# F103-DRV8313.net
KiCad netlist of a schematic drawn in Altium Designer
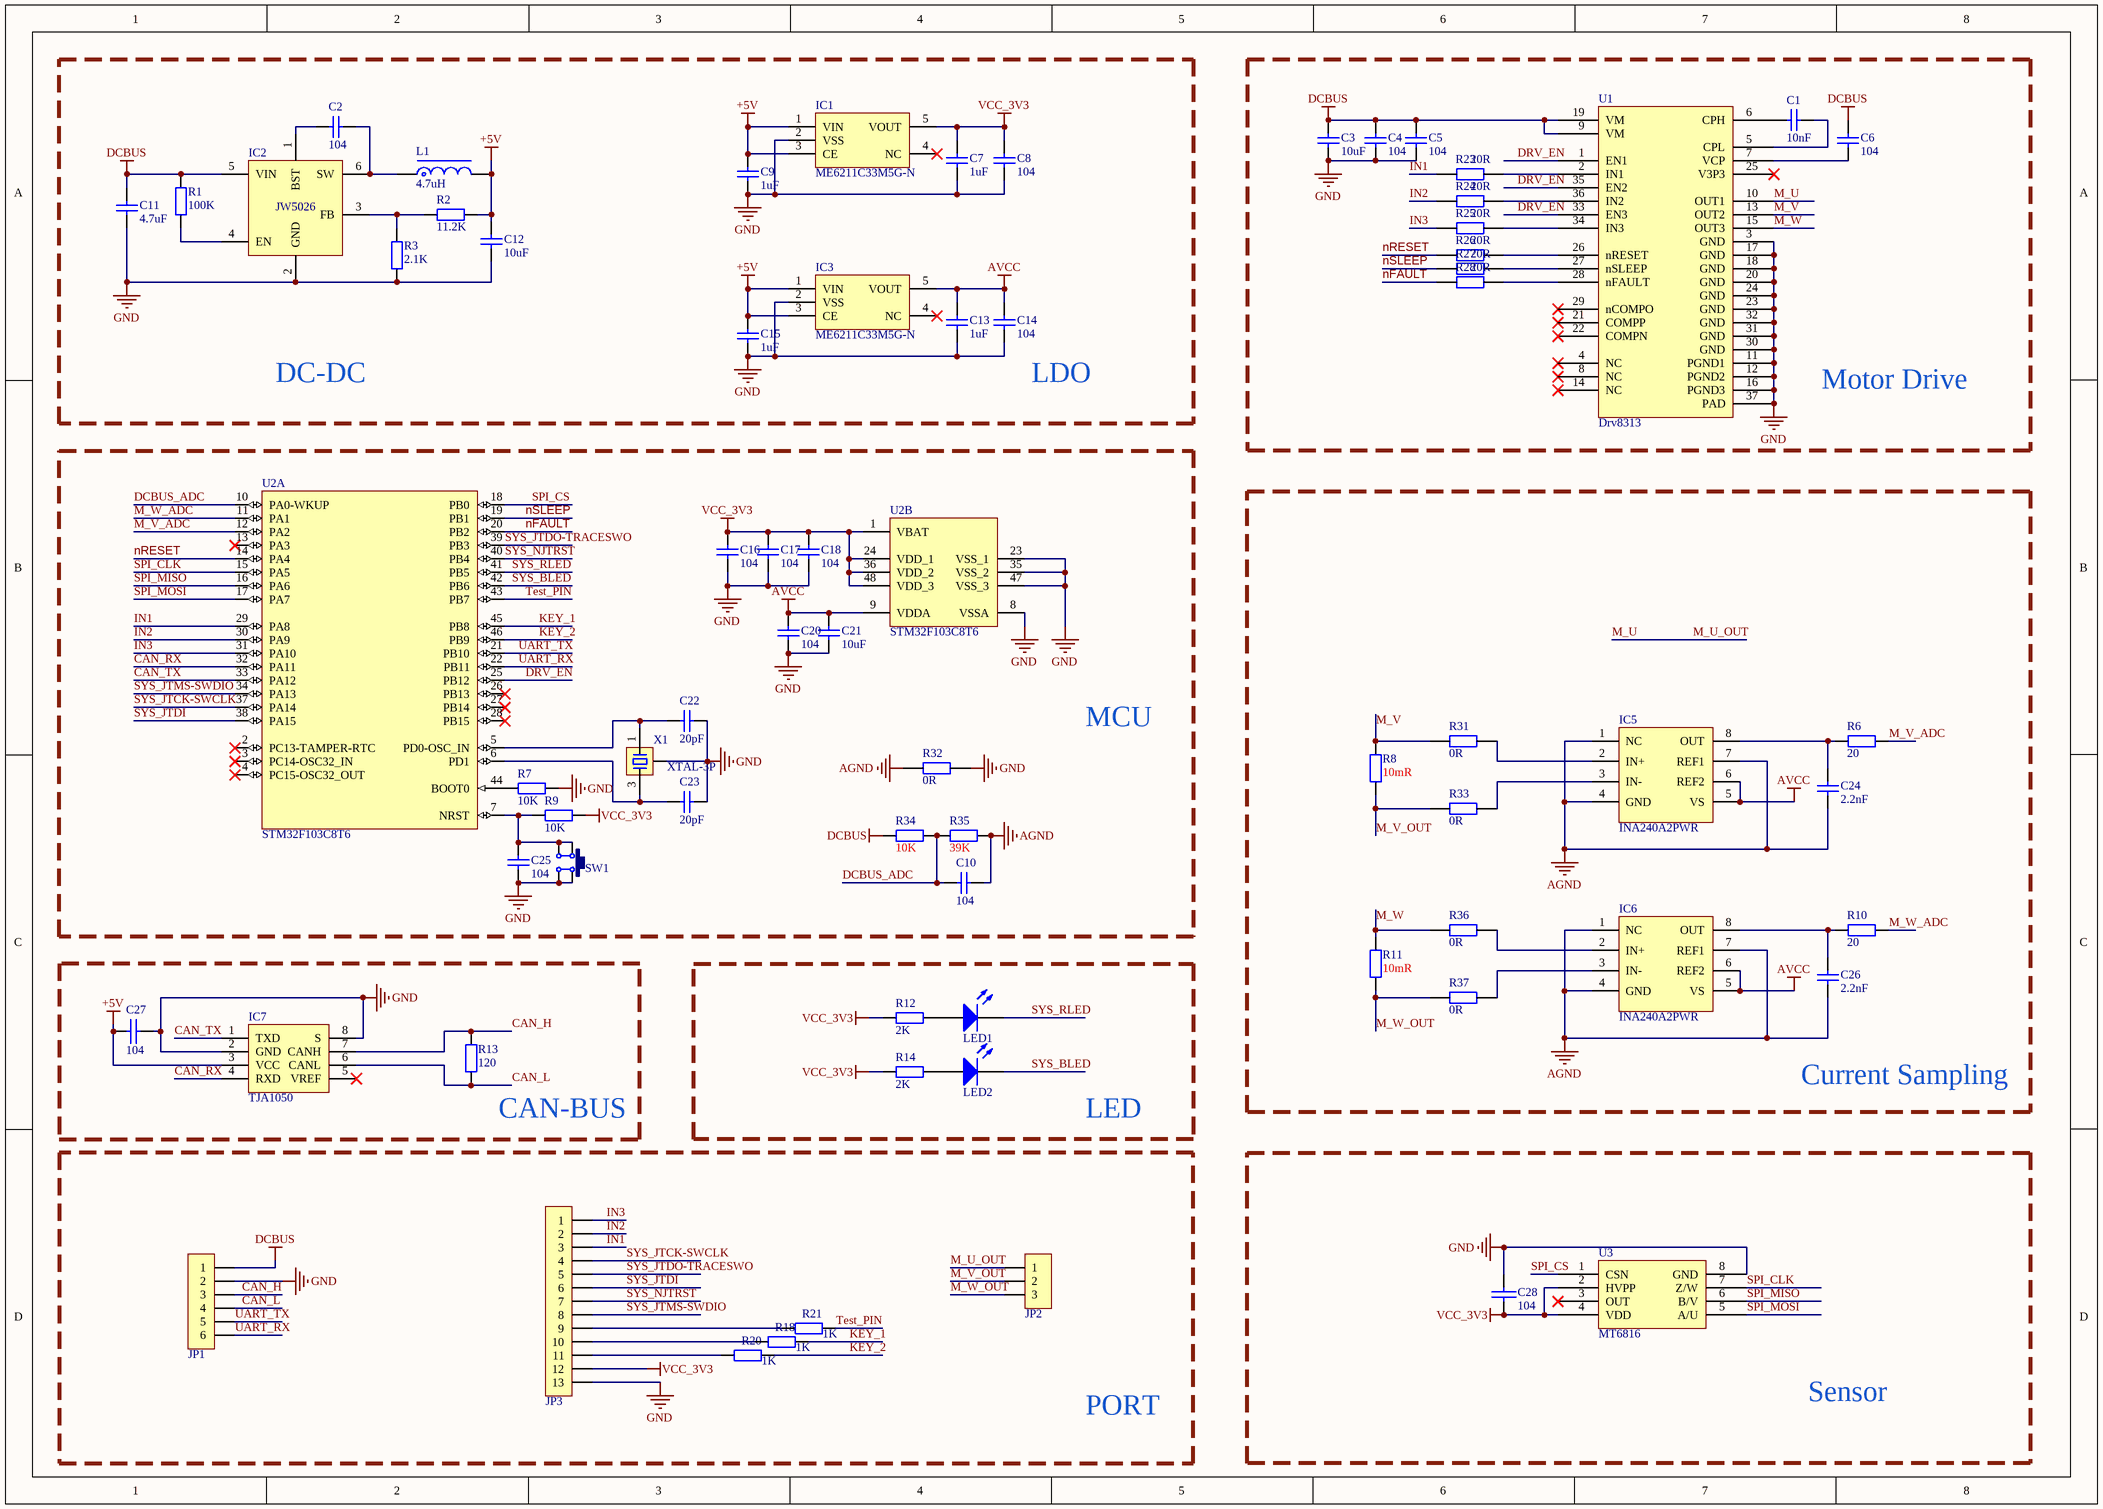
[diagram p0: F103-DRV8313.SchDoc]

(export (version "E")
  (design (tool "Eeschema 10.0.6"))
  (components
    (comp (ref "C1")
      (value "10nF")
      (footprint "C0603_L")
      (description "贴片电容/MLCC电容")
      (libsource (lib "0.1 - 电阻-电容-电感-晶振-晶体-磁珠-电位器-法拉电容-馈通电容") (part "C"))
    )
    (comp (ref "C2")
      (value "104")
      (footprint "C0603_L")
      (description "贴片电容/MLCC电容")
      (libsource (lib "0.1 - 电阻-电容-电感-晶振-晶体-磁珠-电位器-法拉电容-馈通电容") (part "C"))
    )
    (comp (ref "C3")
      (value "10uF")
      (footprint "C0603_L")
      (description "贴片电容/MLCC电容")
      (libsource (lib "0.1 - 电阻-电容-电感-晶振-晶体-磁珠-电位器-法拉电容-馈通电容") (part "C"))
    )
    (comp (ref "C4")
      (value "104")
      (footprint "C0603_L")
      (description "贴片电容/MLCC电容")
      (libsource (lib "0.1 - 电阻-电容-电感-晶振-晶体-磁珠-电位器-法拉电容-馈通电容") (part "C"))
    )
    (comp (ref "C5")
      (value "104")
      (footprint "C0603_L")
      (description "贴片电容/MLCC电容")
      (libsource (lib "0.1 - 电阻-电容-电感-晶振-晶体-磁珠-电位器-法拉电容-馈通电容") (part "C"))
    )
    (comp (ref "C6")
      (value "104")
      (footprint "C0603_L")
      (description "贴片电容/MLCC电容")
      (libsource (lib "0.1 - 电阻-电容-电感-晶振-晶体-磁珠-电位器-法拉电容-馈通电容") (part "C"))
    )
    (comp (ref "C7")
      (value "1uF")
      (footprint "C0603_L")
      (description "贴片电容/MLCC电容")
      (libsource (lib "0.1 - 电阻-电容-电感-晶振-晶体-磁珠-电位器-法拉电容-馈通电容") (part "C"))
    )
    (comp (ref "C8")
      (value "104")
      (footprint "C0603_L")
      (description "贴片电容/MLCC电容")
      (libsource (lib "0.1 - 电阻-电容-电感-晶振-晶体-磁珠-电位器-法拉电容-馈通电容") (part "C"))
    )
    (comp (ref "C9")
      (value "1uF")
      (footprint "C0603_L")
      (description "贴片电容/MLCC电容")
      (libsource (lib "0.1 - 电阻-电容-电感-晶振-晶体-磁珠-电位器-法拉电容-馈通电容") (part "C"))
    )
    (comp (ref "C10")
      (value "104")
      (footprint "C0402_L")
      (description "贴片电容/MLCC电容")
      (libsource (lib "0.1 - 电阻-电容-电感-晶振-晶体-磁珠-电位器-法拉电容-馈通电容") (part "C"))
    )
    (comp (ref "C11")
      (value "4.7uF")
      (footprint "C0603_L")
      (description "贴片电容/MLCC电容")
      (libsource (lib "0.1 - 电阻-电容-电感-晶振-晶体-磁珠-电位器-法拉电容-馈通电容") (part "C"))
    )
    (comp (ref "C12")
      (value "10uF")
      (footprint "C0603_L")
      (description "贴片电容/MLCC电容")
      (libsource (lib "0.1 - 电阻-电容-电感-晶振-晶体-磁珠-电位器-法拉电容-馈通电容") (part "C"))
    )
    (comp (ref "C13")
      (value "1uF")
      (footprint "C0603_L")
      (description "贴片电容/MLCC电容")
      (libsource (lib "0.1 - 电阻-电容-电感-晶振-晶体-磁珠-电位器-法拉电容-馈通电容") (part "C"))
    )
    (comp (ref "C14")
      (value "104")
      (footprint "C0603_L")
      (description "贴片电容/MLCC电容")
      (libsource (lib "0.1 - 电阻-电容-电感-晶振-晶体-磁珠-电位器-法拉电容-馈通电容") (part "C"))
    )
    (comp (ref "C15")
      (value "1uF")
      (footprint "C0603_L")
      (description "贴片电容/MLCC电容")
      (libsource (lib "0.1 - 电阻-电容-电感-晶振-晶体-磁珠-电位器-法拉电容-馈通电容") (part "C"))
    )
    (comp (ref "C16")
      (value "104")
      (footprint "C0402_L")
      (description "贴片电容/MLCC电容")
      (libsource (lib "0.1 - 电阻-电容-电感-晶振-晶体-磁珠-电位器-法拉电容-馈通电容") (part "C"))
    )
    (comp (ref "C17")
      (value "104")
      (footprint "C0402_L")
      (description "贴片电容/MLCC电容")
      (libsource (lib "0.1 - 电阻-电容-电感-晶振-晶体-磁珠-电位器-法拉电容-馈通电容") (part "C"))
    )
    (comp (ref "C18")
      (value "104")
      (footprint "C0402_L")
      (description "贴片电容/MLCC电容")
      (libsource (lib "0.1 - 电阻-电容-电感-晶振-晶体-磁珠-电位器-法拉电容-馈通电容") (part "C"))
    )
    (comp (ref "C20")
      (value "104")
      (footprint "C0402_L")
      (description "贴片电容/MLCC电容")
      (libsource (lib "0.1 - 电阻-电容-电感-晶振-晶体-磁珠-电位器-法拉电容-馈通电容") (part "C"))
    )
    (comp (ref "C21")
      (value "10uF")
      (footprint "C0402_L")
      (description "贴片电容/MLCC电容")
      (libsource (lib "0.1 - 电阻-电容-电感-晶振-晶体-磁珠-电位器-法拉电容-馈通电容") (part "C"))
    )
    (comp (ref "C22")
      (value "20pF")
      (footprint "C0402_L")
      (description "贴片电容/MLCC电容")
      (libsource (lib "0.1 - 电阻-电容-电感-晶振-晶体-磁珠-电位器-法拉电容-馈通电容") (part "C"))
    )
    (comp (ref "C23")
      (value "20pF")
      (footprint "C0402_L")
      (description "贴片电容/MLCC电容")
      (libsource (lib "0.1 - 电阻-电容-电感-晶振-晶体-磁珠-电位器-法拉电容-馈通电容") (part "C"))
    )
    (comp (ref "C24")
      (value "2.2nF")
      (footprint "C0402_L")
      (description "贴片电容/MLCC电容")
      (libsource (lib "0.1 - 电阻-电容-电感-晶振-晶体-磁珠-电位器-法拉电容-馈通电容") (part "C"))
    )
    (comp (ref "C25")
      (value "104")
      (footprint "C0402_L")
      (description "贴片电容/MLCC电容")
      (libsource (lib "0.1 - 电阻-电容-电感-晶振-晶体-磁珠-电位器-法拉电容-馈通电容") (part "C"))
    )
    (comp (ref "C26")
      (value "2.2nF")
      (footprint "C0402_L")
      (description "贴片电容/MLCC电容")
      (libsource (lib "0.1 - 电阻-电容-电感-晶振-晶体-磁珠-电位器-法拉电容-馈通电容") (part "C"))
    )
    (comp (ref "C27")
      (value "104")
      (footprint "C0402_L")
      (description "Capacitor")
      (libsource (lib "SCHLIB") (part "Capacitor"))
    )
    (comp (ref "C28")
      (value "104")
      (footprint "C0402_L")
      (description "Capacitor")
      (libsource (lib "SCHLIB") (part "Capacitor"))
    )
    (comp (ref "IC1")
      (value "ME6211C33M5G-N")
      (footprint "SOT23-5N")
      (libsource (lib "1.0 - 常见芯片") (part "ME6211C33M5G-N"))
    )
    (comp (ref "IC2")
      (value "JW5026")
      (footprint "SOT23-6M")
      (libsource (lib "1.0 - 常见芯片") (part "JW5026 40V 1A"))
    )
    (comp (ref "IC3")
      (value "ME6211C33M5G-N")
      (footprint "SOT23-5N")
      (libsource (lib "1.0 - 常见芯片") (part "ME6211C33M5G-N"))
    )
    (comp (ref "IC5")
      (value "INA240A2PWR")
      (footprint "TSSOP8_N")
      (description "运放芯片")
      (libsource (lib "1.0 - 常见芯片") (part "INA240A2PWR"))
    )
    (comp (ref "IC6")
      (value "INA240A2PWR")
      (footprint "TSSOP8_N")
      (description "运放芯片")
      (libsource (lib "1.0 - 常见芯片") (part "INA240A2PWR"))
    )
    (comp (ref "IC7")
      (value "TJA1050")
      (footprint "SOP8_N")
      (description "CAN总线收发芯片")
      (libsource (lib "1.0 - 常见芯片") (part "TJA1050"))
    )
    (comp (ref "JP1")
      (value "HDR-1X6")
      (footprint "GH-1.25-6P")
      (description "6P连接器")
      (libsource (lib "5.1 - 1.25mm连接器(FPC1.25_GH1.25_MX1.25)") (part "Header 6"))
    )
    (comp (ref "JP2")
      (value "CON-3P")
      (footprint "SH1.0-WT-3P")
      (description "3P连接器")
      (libsource (lib "5.0 - 1.00mm连接器(FPC1.0_SH1.0_1.0排针排母)") (part "Header 3"))
    )
    (comp (ref "JP3")
      (value "HDR-1X13")
      (footprint "FPC0.5-WT-13P")
      (description "13P连接器")
      (libsource (lib "5.1 - 1.25mm连接器(FPC1.25_GH1.25_MX1.25)") (part "Header 13"))
    )
    (comp (ref "L1")
      (value "4.7uH")
      (footprint "CD31")
      (description "功率屏蔽电感")
      (libsource (lib "0.1 - 电阻-电容-电感") (part "L-CDRH"))
    )
    (comp (ref "LED1")
      (value "LED")
      (footprint "LED 0603B")
      (description "发光二极管")
      (libsource (lib "0.3 - LED发光二极管") (part "LED"))
    )
    (comp (ref "LED2")
      (value "LED")
      (footprint "LED 0603B")
      (description "发光二极管")
      (libsource (lib "0.3 - LED发光二极管") (part "LED"))
    )
    (comp (ref "R1")
      (value "100K")
      (footprint "R 0402_L")
      (description "贴片电阻")
      (libsource (lib "0.1 - 电阻-电容-电感") (part "R"))
    )
    (comp (ref "R2")
      (value "11.2K")
      (footprint "R 0402_L")
      (description "贴片电阻")
      (libsource (lib "0.1 - 电阻-电容-电感") (part "R"))
    )
    (comp (ref "R3")
      (value "2.1K")
      (footprint "R 0402_L")
      (description "贴片电阻")
      (libsource (lib "0.1 - 电阻-电容-电感") (part "R"))
    )
    (comp (ref "R6")
      (value "20")
      (footprint "R 0402_L")
      (description "贴片电阻")
      (libsource (lib "0.1 - 电阻-电容-电感") (part "R"))
    )
    (comp (ref "R7")
      (value "10K")
      (footprint "R0402_L")
      (description "贴片电阻")
      (libsource (lib "0.1 - 电阻-电容-电感-晶振-晶体-磁珠-电位器-法拉电容-馈通电容") (part "R"))
    )
    (comp (ref "R8")
      (value "10mR")
      (footprint "R0805_L")
      (description "电流检测电阻")
      (libsource (lib "0.1 - 电阻-电容-电感") (part "R-I"))
    )
    (comp (ref "R9")
      (value "10K")
      (footprint "R0402_L")
      (description "贴片电阻")
      (libsource (lib "0.1 - 电阻-电容-电感-晶振-晶体-磁珠-电位器-法拉电容-馈通电容") (part "R"))
    )
    (comp (ref "R10")
      (value "20")
      (footprint "R 0402_L")
      (description "贴片电阻")
      (libsource (lib "0.1 - 电阻-电容-电感") (part "R"))
    )
    (comp (ref "R11")
      (value "10mR")
      (footprint "R0805_L")
      (description "电流检测电阻")
      (libsource (lib "0.1 - 电阻-电容-电感") (part "R-I"))
    )
    (comp (ref "R12")
      (value "2K")
      (footprint "R 0402_L")
      (description "贴片电阻")
      (libsource (lib "0.1 - 电阻-电容-电感") (part "R"))
    )
    (comp (ref "R13")
      (value "120")
      (footprint "R0402_L")
      (description "贴片电阻")
      (libsource (lib "0.1 - 电阻-电容-电感") (part "R"))
    )
    (comp (ref "R14")
      (value "2K")
      (footprint "R 0402_L")
      (description "贴片电阻")
      (libsource (lib "0.1 - 电阻-电容-电感") (part "R"))
    )
    (comp (ref "R18")
      (value "1K")
      (footprint "R0402_L")
      (description "贴片电阻")
      (libsource (lib "0.1 - 电阻-电容-电感") (part "R"))
    )
    (comp (ref "R20")
      (value "1K")
      (footprint "R0402_L")
      (description "贴片电阻")
      (libsource (lib "0.1 - 电阻-电容-电感") (part "R"))
    )
    (comp (ref "R21")
      (value "1K")
      (footprint "R0402_L")
      (description "贴片电阻")
      (libsource (lib "0.1 - 电阻-电容-电感") (part "R"))
    )
    (comp (ref "R23")
      (value "20R")
      (footprint "R0402_L")
      (description "10K")
      (libsource (lib "SCHLIB") (part "RES_R"))
    )
    (comp (ref "R24")
      (value "20R")
      (footprint "R0402_L")
      (description "10K")
      (libsource (lib "SCHLIB") (part "RES_R"))
    )
    (comp (ref "R25")
      (value "20R")
      (footprint "R0402_L")
      (description "10K")
      (libsource (lib "SCHLIB") (part "RES_R"))
    )
    (comp (ref "R26")
      (value "20R")
      (footprint "R0402_L")
      (description "10K")
      (libsource (lib "SCHLIB") (part "RES_R"))
    )
    (comp (ref "R27")
      (value "20R")
      (footprint "R0402_L")
      (description "10K")
      (libsource (lib "SCHLIB") (part "RES_R"))
    )
    (comp (ref "R28")
      (value "20R")
      (footprint "R0402_L")
      (description "10K")
      (libsource (lib "SCHLIB") (part "RES_R"))
    )
    (comp (ref "R31")
      (value "0R")
      (footprint "R0402_L")
      (description "10K")
      (libsource (lib "SCHLIB") (part "RES_R"))
    )
    (comp (ref "R32")
      (value "0R")
      (footprint "R0402_L")
      (description "10K")
      (libsource (lib "SCHLIB") (part "RES_R"))
    )
    (comp (ref "R33")
      (value "0R")
      (footprint "R0402_L")
      (description "10K")
      (libsource (lib "SCHLIB") (part "RES_R"))
    )
    (comp (ref "R34")
      (value "10K")
      (footprint "R0402_L")
      (description "贴片电阻")
      (libsource (lib "0.1 - 电阻-电容-电感-晶振-晶体-磁珠-电位器-法拉电容-馈通电容") (part "R"))
    )
    (comp (ref "R35")
      (value "39K")
      (footprint "R0402_L")
      (description "贴片电阻")
      (libsource (lib "0.1 - 电阻-电容-电感-晶振-晶体-磁珠-电位器-法拉电容-馈通电容") (part "R"))
    )
    (comp (ref "R36")
      (value "0R")
      (footprint "R0402_L")
      (description "10K")
      (libsource (lib "SCHLIB") (part "RES_R"))
    )
    (comp (ref "R37")
      (value "0R")
      (footprint "R0402_L")
      (description "10K")
      (libsource (lib "SCHLIB") (part "RES_R"))
    )
    (comp (ref "SW1")
      (value "6x6x5")
      (footprint "TSW SMD-2.9*3.9*2")
      (description "贴片6x6轻触开关")
      (libsource (lib "0.7 - 常用按键-开关") (part "TSW SMD-6x6"))
    )
    (comp (ref "U1")
      (value "Drv8313")
      (footprint "VFQFPN36_N")
      (libsource (lib "4.1 - 未分类器件") (part "Drv8313"))
    )
    (comp (ref "U2")
      (value "STM32F103C8T6")
      (footprint "LQFP48_N")
      (libsource (lib "2.4 - STM32 F1系列单片机") (part "STM32F103C8T6"))
    )
    (comp (ref "U3") (value "MT6816") (footprint "SOP8_N") (libsource (lib "4.1 - 未分类器件") (part "MT6816")))
    (comp (ref "X1")
      (value "XTAL-3P")
      (footprint "SMD3213-3P")
      (description "三脚无源晶振")
      (libsource (lib "2.0 - 保险丝-晶振-光耦") (part "XTAL-3P"))
    )
  )
  (nets
    (net (code "1") (name "+5V") (class "Default")
      (node (ref "C12") (pin "2") (pinfunction "2_2") (pintype "passive"))
      (node (ref "C15") (pin "2") (pinfunction "2_2") (pintype "passive"))
      (node (ref "C27") (pin "1") (pinfunction "1_1") (pintype "passive"))
      (node (ref "C9") (pin "2") (pinfunction "2_2") (pintype "passive"))
      (node (ref "IC1") (pin "1") (pinfunction "VIN_1") (pintype "passive"))
      (node (ref "IC1") (pin "3") (pinfunction "CE_3") (pintype "passive"))
      (node (ref "IC3") (pin "1") (pinfunction "VIN_1") (pintype "passive"))
      (node (ref "IC3") (pin "3") (pinfunction "CE_3") (pintype "passive"))
      (node (ref "IC7") (pin "3") (pinfunction "VCC_3") (pintype "passive"))
      (node (ref "L1") (pin "2") (pinfunction "2_2") (pintype "passive"))
      (node (ref "R2") (pin "1") (pinfunction "1_1") (pintype "passive"))
    )
    (net (code "2") (name "/CAN_H") (class "Default")
      (node (ref "IC7") (pin "7") (pinfunction "CANH_7") (pintype "passive"))
      (node (ref "JP1") (pin "3") (pinfunction "3_3") (pintype "passive"))
      (node (ref "R13") (pin "2") (pinfunction "2_2") (pintype "passive"))
    )
    (net (code "3") (name "/CAN_L") (class "Default")
      (node (ref "IC7") (pin "6") (pinfunction "CANL_6") (pintype "passive"))
      (node (ref "JP1") (pin "4") (pinfunction "4_4") (pintype "passive"))
      (node (ref "R13") (pin "1") (pinfunction "1_1") (pintype "passive"))
    )
    (net (code "4") (name "/CAN_RX") (class "Default")
      (node (ref "IC7") (pin "4") (pinfunction "RXD_4") (pintype "passive"))
      (node (ref "U2") (pin "32") (pinfunction "PA11_32") (pintype "bidirectional"))
    )
    (net (code "5") (name "/CAN_TX") (class "Default")
      (node (ref "IC7") (pin "1") (pinfunction "TXD_1") (pintype "passive"))
      (node (ref "U2") (pin "33") (pinfunction "PA12_33") (pintype "bidirectional"))
    )
    (net (code "6") (name "/DCBUS_ADC") (class "Default")
      (node (ref "C10") (pin "2") (pinfunction "2_2") (pintype "passive"))
      (node (ref "R34") (pin "1") (pinfunction "1_1") (pintype "passive"))
      (node (ref "R35") (pin "2") (pinfunction "2_2") (pintype "passive"))
      (node (ref "U2") (pin "10") (pinfunction "PA0-WKUP_10") (pintype "bidirectional"))
    )
    (net (code "7") (name "/DRV_EN") (class "Default")
      (node (ref "U1") (pin "1") (pinfunction "EN1_1") (pintype "passive"))
      (node (ref "U1") (pin "33") (pinfunction "EN3_33") (pintype "passive"))
      (node (ref "U1") (pin "35") (pinfunction "EN2_35") (pintype "passive"))
      (node (ref "U2") (pin "25") (pinfunction "PB12_25") (pintype "bidirectional"))
    )
    (net (code "8") (name "/IN1") (class "Default")
      (node (ref "JP3") (pin "3") (pinfunction "3_3") (pintype "passive"))
      (node (ref "R23") (pin "1") (pinfunction "1_1") (pintype "passive"))
      (node (ref "U2") (pin "29") (pinfunction "PA8_29") (pintype "bidirectional"))
    )
    (net (code "9") (name "/IN2") (class "Default")
      (node (ref "JP3") (pin "2") (pinfunction "2_2") (pintype "passive"))
      (node (ref "R24") (pin "1") (pinfunction "1_1") (pintype "passive"))
      (node (ref "U2") (pin "30") (pinfunction "PA9_30") (pintype "bidirectional"))
    )
    (net (code "10") (name "/IN3") (class "Default")
      (node (ref "JP3") (pin "1") (pinfunction "1_1") (pintype "passive"))
      (node (ref "R25") (pin "1") (pinfunction "1_1") (pintype "passive"))
      (node (ref "U2") (pin "31") (pinfunction "PA10_31") (pintype "bidirectional"))
    )
    (net (code "11") (name "/KEY_1") (class "Default")
      (node (ref "R18") (pin "1") (pinfunction "1_1") (pintype "passive"))
      (node (ref "U2") (pin "45") (pinfunction "PB8_45") (pintype "bidirectional"))
    )
    (net (code "12") (name "/KEY_2") (class "Default")
      (node (ref "R20") (pin "1") (pinfunction "1_1") (pintype "passive"))
      (node (ref "U2") (pin "46") (pinfunction "PB9_46") (pintype "bidirectional"))
    )
    (net (code "13") (name "/M_U") (class "Default")
      (node (ref "JP2") (pin "1") (pinfunction "1_1") (pintype "passive"))
      (node (ref "U1") (pin "10") (pinfunction "OUT1_10") (pintype "passive"))
    )
    (net (code "14") (name "/M_V") (class "Default")
      (node (ref "R31") (pin "1") (pinfunction "1_1") (pintype "passive"))
      (node (ref "R8") (pin "1") (pinfunction "1_1") (pintype "passive"))
      (node (ref "U1") (pin "13") (pinfunction "OUT2_13") (pintype "passive"))
    )
    (net (code "15") (name "/M_V_ADC") (class "Default")
      (node (ref "R6") (pin "1") (pinfunction "1_1") (pintype "passive"))
      (node (ref "U2") (pin "12") (pinfunction "PA2_12") (pintype "bidirectional"))
    )
    (net (code "16") (name "/M_V_OUT") (class "Default")
      (node (ref "JP2") (pin "2") (pinfunction "2_2") (pintype "passive"))
      (node (ref "R33") (pin "1") (pinfunction "1_1") (pintype "passive"))
      (node (ref "R8") (pin "2") (pinfunction "2_2") (pintype "passive"))
    )
    (net (code "17") (name "/M_W") (class "Default")
      (node (ref "R11") (pin "1") (pinfunction "1_1") (pintype "passive"))
      (node (ref "R36") (pin "1") (pinfunction "1_1") (pintype "passive"))
      (node (ref "U1") (pin "15") (pinfunction "OUT3_15") (pintype "passive"))
    )
    (net (code "18") (name "/M_W_ADC") (class "Default")
      (node (ref "R10") (pin "1") (pinfunction "1_1") (pintype "passive"))
      (node (ref "U2") (pin "11") (pinfunction "PA1_11") (pintype "bidirectional"))
    )
    (net (code "19") (name "/M_W_OUT") (class "Default")
      (node (ref "JP2") (pin "3") (pinfunction "3_3") (pintype "passive"))
      (node (ref "R11") (pin "2") (pinfunction "2_2") (pintype "passive"))
      (node (ref "R37") (pin "1") (pinfunction "1_1") (pintype "passive"))
    )
    (net (code "20") (name "/SPI_CLK") (class "Default")
      (node (ref "U2") (pin "15") (pinfunction "PA5_15") (pintype "bidirectional"))
      (node (ref "U3") (pin "7") (pinfunction "Z/W_7") (pintype "passive"))
    )
    (net (code "21") (name "/SPI_CS") (class "Default")
      (node (ref "U2") (pin "18") (pinfunction "PB0_18") (pintype "bidirectional"))
      (node (ref "U3") (pin "1") (pinfunction "CSN_1") (pintype "passive"))
    )
    (net (code "22") (name "/SPI_MISO") (class "Default")
      (node (ref "U2") (pin "16") (pinfunction "PA6_16") (pintype "bidirectional"))
      (node (ref "U3") (pin "6") (pinfunction "B/V_6") (pintype "passive"))
    )
    (net (code "23") (name "/SPI_MOSI") (class "Default")
      (node (ref "U2") (pin "17") (pinfunction "PA7_17") (pintype "bidirectional"))
      (node (ref "U3") (pin "5") (pinfunction "A/U_5") (pintype "passive"))
    )
    (net (code "24") (name "/SYS_BLED") (class "Default")
      (node (ref "LED2") (pin "2") (pinfunction "K_2") (pintype "passive"))
      (node (ref "U2") (pin "42") (pinfunction "PB6_42") (pintype "bidirectional"))
    )
    (net (code "25") (name "/SYS_JTCK-SWCLK") (class "Default")
      (node (ref "JP3") (pin "4") (pinfunction "4_4") (pintype "passive"))
      (node (ref "U2") (pin "37") (pinfunction "PA14_37") (pintype "bidirectional"))
    )
    (net (code "26") (name "/SYS_JTDI") (class "Default")
      (node (ref "JP3") (pin "6") (pinfunction "6_6") (pintype "passive"))
      (node (ref "U2") (pin "38") (pinfunction "PA15_38") (pintype "bidirectional"))
    )
    (net (code "27") (name "/SYS_JTDO-TRACESWO") (class "Default")
      (node (ref "JP3") (pin "5") (pinfunction "5_5") (pintype "passive"))
      (node (ref "U2") (pin "39") (pinfunction "PB3_39") (pintype "bidirectional"))
    )
    (net (code "28") (name "/SYS_JTMS-SWDIO") (class "Default")
      (node (ref "JP3") (pin "8") (pinfunction "8_8") (pintype "passive"))
      (node (ref "U2") (pin "34") (pinfunction "PA13_34") (pintype "bidirectional"))
    )
    (net (code "29") (name "/SYS_NJTRST") (class "Default")
      (node (ref "JP3") (pin "7") (pinfunction "7_7") (pintype "passive"))
      (node (ref "U2") (pin "40") (pinfunction "PB4_40") (pintype "bidirectional"))
    )
    (net (code "30") (name "/SYS_RLED") (class "Default")
      (node (ref "LED1") (pin "2") (pinfunction "K_2") (pintype "passive"))
      (node (ref "U2") (pin "41") (pinfunction "PB5_41") (pintype "bidirectional"))
    )
    (net (code "31") (name "/Test_PIN") (class "Default")
      (node (ref "R21") (pin "1") (pinfunction "1_1") (pintype "passive"))
      (node (ref "U2") (pin "43") (pinfunction "PB7_43") (pintype "bidirectional"))
    )
    (net (code "32") (name "/UART_RX") (class "Default")
      (node (ref "JP1") (pin "6") (pinfunction "6_6") (pintype "passive"))
      (node (ref "U2") (pin "22") (pinfunction "PB11_22") (pintype "bidirectional"))
    )
    (net (code "33") (name "/UART_TX") (class "Default")
      (node (ref "JP1") (pin "5") (pinfunction "5_5") (pintype "passive"))
      (node (ref "U2") (pin "21") (pinfunction "PB10_21") (pintype "bidirectional"))
    )
    (net (code "34") (name "/nFAULT") (class "Default")
      (node (ref "R28") (pin "1") (pinfunction "1_1") (pintype "passive"))
      (node (ref "U2") (pin "20") (pinfunction "PB2_20") (pintype "bidirectional"))
    )
    (net (code "35") (name "/nRESET") (class "Default")
      (node (ref "R26") (pin "1") (pinfunction "1_1") (pintype "passive"))
      (node (ref "U2") (pin "14") (pinfunction "PA4_14") (pintype "bidirectional"))
    )
    (net (code "36") (name "/nSLEEP") (class "Default")
      (node (ref "R27") (pin "1") (pinfunction "1_1") (pintype "passive"))
      (node (ref "U2") (pin "19") (pinfunction "PB1_19") (pintype "bidirectional"))
    )
    (net (code "37") (name "AGND") (class "Default")
      (node (ref "C10") (pin "1") (pinfunction "1_1") (pintype "passive"))
      (node (ref "C24") (pin "1") (pinfunction "1_1") (pintype "passive"))
      (node (ref "C26") (pin "1") (pinfunction "1_1") (pintype "passive"))
      (node (ref "IC5") (pin "1") (pinfunction "NC_1") (pintype "passive"))
      (node (ref "IC5") (pin "4") (pinfunction "GND_4") (pintype "passive"))
      (node (ref "IC5") (pin "7") (pinfunction "REF1_7") (pintype "passive"))
      (node (ref "IC6") (pin "1") (pinfunction "NC_1") (pintype "passive"))
      (node (ref "IC6") (pin "4") (pinfunction "GND_4") (pintype "passive"))
      (node (ref "IC6") (pin "7") (pinfunction "REF1_7") (pintype "passive"))
      (node (ref "R32") (pin "1") (pinfunction "1_1") (pintype "passive"))
      (node (ref "R35") (pin "1") (pinfunction "1_1") (pintype "passive"))
    )
    (net (code "38") (name "AVCC") (class "Default")
      (node (ref "C13") (pin "2") (pinfunction "2_2") (pintype "passive"))
      (node (ref "C14") (pin "2") (pinfunction "2_2") (pintype "passive"))
      (node (ref "C20") (pin "2") (pinfunction "2_2") (pintype "passive"))
      (node (ref "C21") (pin "2") (pinfunction "2_2") (pintype "passive"))
      (node (ref "IC3") (pin "5") (pinfunction "VOUT_5") (pintype "passive"))
      (node (ref "IC5") (pin "5") (pinfunction "VS_5") (pintype "passive"))
      (node (ref "IC5") (pin "6") (pinfunction "REF2_6") (pintype "passive"))
      (node (ref "IC6") (pin "5") (pinfunction "VS_5") (pintype "passive"))
      (node (ref "IC6") (pin "6") (pinfunction "REF2_6") (pintype "passive"))
      (node (ref "U2") (pin "9") (pinfunction "VDDA_9") (pintype "power_in"))
    )
    (net (code "39") (name "DCBUS") (class "Default")
      (node (ref "C11") (pin "2") (pinfunction "2_2") (pintype "passive"))
      (node (ref "C3") (pin "2") (pinfunction "2_2") (pintype "passive"))
      (node (ref "C4") (pin "2") (pinfunction "2_2") (pintype "passive"))
      (node (ref "C5") (pin "2") (pinfunction "2_2") (pintype "passive"))
      (node (ref "C6") (pin "1") (pinfunction "1_1") (pintype "passive"))
      (node (ref "IC2") (pin "5") (pinfunction "VIN_5") (pintype "passive"))
      (node (ref "JP1") (pin "1") (pinfunction "1_1") (pintype "passive"))
      (node (ref "R1") (pin "2") (pinfunction "2_2") (pintype "passive"))
      (node (ref "R34") (pin "2") (pinfunction "2_2") (pintype "passive"))
      (node (ref "U1") (pin "19") (pinfunction "VM_19") (pintype "passive"))
      (node (ref "U1") (pin "9") (pinfunction "VM_9") (pintype "passive"))
    )
    (net (code "40") (name "GND") (class "Default")
      (node (ref "C11") (pin "1") (pinfunction "1_1") (pintype "passive"))
      (node (ref "C12") (pin "1") (pinfunction "1_1") (pintype "passive"))
      (node (ref "C13") (pin "1") (pinfunction "1_1") (pintype "passive"))
      (node (ref "C14") (pin "1") (pinfunction "1_1") (pintype "passive"))
      (node (ref "C15") (pin "1") (pinfunction "1_1") (pintype "passive"))
      (node (ref "C16") (pin "1") (pinfunction "1_1") (pintype "passive"))
      (node (ref "C17") (pin "1") (pinfunction "1_1") (pintype "passive"))
      (node (ref "C18") (pin "1") (pinfunction "1_1") (pintype "passive"))
      (node (ref "C20") (pin "1") (pinfunction "1_1") (pintype "passive"))
      (node (ref "C21") (pin "1") (pinfunction "1_1") (pintype "passive"))
      (node (ref "C22") (pin "1") (pinfunction "1_1") (pintype "passive"))
      (node (ref "C23") (pin "1") (pinfunction "1_1") (pintype "passive"))
      (node (ref "C25") (pin "1") (pinfunction "1_1") (pintype "passive"))
      (node (ref "C27") (pin "2") (pinfunction "2_2") (pintype "passive"))
      (node (ref "C28") (pin "2") (pinfunction "2_2") (pintype "passive"))
      (node (ref "C3") (pin "1") (pinfunction "1_1") (pintype "passive"))
      (node (ref "C4") (pin "1") (pinfunction "1_1") (pintype "passive"))
      (node (ref "C5") (pin "1") (pinfunction "1_1") (pintype "passive"))
      (node (ref "C7") (pin "1") (pinfunction "1_1") (pintype "passive"))
      (node (ref "C8") (pin "1") (pinfunction "1_1") (pintype "passive"))
      (node (ref "C9") (pin "1") (pinfunction "1_1") (pintype "passive"))
      (node (ref "IC1") (pin "2") (pinfunction "VSS_2") (pintype "passive"))
      (node (ref "IC2") (pin "2") (pinfunction "GND_2") (pintype "passive"))
      (node (ref "IC3") (pin "2") (pinfunction "VSS_2") (pintype "passive"))
      (node (ref "IC7") (pin "2") (pinfunction "GND_2") (pintype "passive"))
      (node (ref "IC7") (pin "8") (pinfunction "S_8") (pintype "passive"))
      (node (ref "JP1") (pin "2") (pinfunction "2_2") (pintype "passive"))
      (node (ref "JP3") (pin "13") (pinfunction "13_13") (pintype "passive"))
      (node (ref "R3") (pin "1") (pinfunction "1_1") (pintype "passive"))
      (node (ref "R32") (pin "2") (pinfunction "2_2") (pintype "passive"))
      (node (ref "R7") (pin "2") (pinfunction "2_2") (pintype "passive"))
      (node (ref "SW1") (pin "2") (pinfunction "2_2") (pintype "passive"))
      (node (ref "U1") (pin "11") (pinfunction "PGND1_11") (pintype "passive"))
      (node (ref "U1") (pin "12") (pinfunction "PGND2_12") (pintype "passive"))
      (node (ref "U1") (pin "16") (pinfunction "PGND3_16") (pintype "passive"))
      (node (ref "U1") (pin "17") (pinfunction "GND_17") (pintype "passive"))
      (node (ref "U1") (pin "18") (pinfunction "GND_18") (pintype "passive"))
      (node (ref "U1") (pin "20") (pinfunction "GND_20") (pintype "passive"))
      (node (ref "U1") (pin "23") (pinfunction "GND_23") (pintype "passive"))
      (node (ref "U1") (pin "24") (pinfunction "GND_24") (pintype "passive"))
      (node (ref "U1") (pin "3") (pinfunction "GND_3") (pintype "passive"))
      (node (ref "U1") (pin "30") (pinfunction "GND_30") (pintype "passive"))
      (node (ref "U1") (pin "31") (pinfunction "GND_31") (pintype "passive"))
      (node (ref "U1") (pin "32") (pinfunction "GND_32") (pintype "passive"))
      (node (ref "U1") (pin "37") (pinfunction "PAD_37") (pintype "passive"))
      (node (ref "U2") (pin "23") (pinfunction "VSS_1_23") (pintype "power_in"))
      (node (ref "U2") (pin "35") (pinfunction "VSS_2_35") (pintype "power_in"))
      (node (ref "U2") (pin "47") (pinfunction "VSS_3_47") (pintype "power_in"))
      (node (ref "U2") (pin "8") (pinfunction "VSSA_8") (pintype "power_in"))
      (node (ref "U3") (pin "8") (pinfunction "GND_8") (pintype "passive"))
      (node (ref "X1") (pin "2") (pinfunction "2_2") (pintype "passive"))
    )
    (net (code "41") (name "Net-(IC2-BST)") (class "Default")
      (node (ref "C2") (pin "1") (pinfunction "1_1") (pintype "passive"))
      (node (ref "IC2") (pin "1") (pinfunction "BST_1") (pintype "passive"))
    )
    (net (code "42") (name "Net-(IC2-EN)") (class "Default")
      (node (ref "IC2") (pin "4") (pinfunction "EN_4") (pintype "passive"))
      (node (ref "R1") (pin "1") (pinfunction "1_1") (pintype "passive"))
    )
    (net (code "43") (name "Net-(IC2-FB)") (class "Default")
      (node (ref "IC2") (pin "3") (pinfunction "FB_3") (pintype "passive"))
      (node (ref "R2") (pin "2") (pinfunction "2_2") (pintype "passive"))
      (node (ref "R3") (pin "2") (pinfunction "2_2") (pintype "passive"))
    )
    (net (code "44") (name "Net-(IC2-SW)") (class "Default")
      (node (ref "C2") (pin "2") (pinfunction "2_2") (pintype "passive"))
      (node (ref "IC2") (pin "6") (pinfunction "SW_6") (pintype "passive"))
      (node (ref "L1") (pin "1") (pinfunction "1_1") (pintype "passive"))
    )
    (net (code "45") (name "Net-(IC5-IN+)") (class "Default")
      (node (ref "IC5") (pin "2") (pinfunction "IN+_2") (pintype "passive"))
      (node (ref "R31") (pin "2") (pinfunction "2_2") (pintype "passive"))
    )
    (net (code "46") (name "Net-(IC5-IN-)") (class "Default")
      (node (ref "IC5") (pin "3") (pinfunction "IN-_3") (pintype "passive"))
      (node (ref "R33") (pin "2") (pinfunction "2_2") (pintype "passive"))
    )
    (net (code "47") (name "Net-(IC5-OUT)") (class "Default")
      (node (ref "C24") (pin "2") (pinfunction "2_2") (pintype "passive"))
      (node (ref "IC5") (pin "8") (pinfunction "OUT_8") (pintype "passive"))
      (node (ref "R6") (pin "2") (pinfunction "2_2") (pintype "passive"))
    )
    (net (code "48") (name "Net-(IC6-IN+)") (class "Default")
      (node (ref "IC6") (pin "2") (pinfunction "IN+_2") (pintype "passive"))
      (node (ref "R36") (pin "2") (pinfunction "2_2") (pintype "passive"))
    )
    (net (code "49") (name "Net-(IC6-IN-)") (class "Default")
      (node (ref "IC6") (pin "3") (pinfunction "IN-_3") (pintype "passive"))
      (node (ref "R37") (pin "2") (pinfunction "2_2") (pintype "passive"))
    )
    (net (code "50") (name "Net-(IC6-OUT)") (class "Default")
      (node (ref "C26") (pin "2") (pinfunction "2_2") (pintype "passive"))
      (node (ref "IC6") (pin "8") (pinfunction "OUT_8") (pintype "passive"))
      (node (ref "R10") (pin "2") (pinfunction "2_2") (pintype "passive"))
    )
    (net (code "51") (name "Net-(JP3-Pad9)") (class "Default")
      (node (ref "JP3") (pin "9") (pinfunction "9_9") (pintype "passive"))
      (node (ref "R21") (pin "2") (pinfunction "2_2") (pintype "passive"))
    )
    (net (code "52") (name "Net-(JP3-Pad10)") (class "Default")
      (node (ref "JP3") (pin "10") (pinfunction "10_10") (pintype "passive"))
      (node (ref "R18") (pin "2") (pinfunction "2_2") (pintype "passive"))
    )
    (net (code "53") (name "Net-(JP3-Pad11)") (class "Default")
      (node (ref "JP3") (pin "11") (pinfunction "11_11") (pintype "passive"))
      (node (ref "R20") (pin "2") (pinfunction "2_2") (pintype "passive"))
    )
    (net (code "54") (name "Net-(LED1-A)") (class "Default")
      (node (ref "LED1") (pin "1") (pinfunction "A_1") (pintype "passive"))
      (node (ref "R12") (pin "2") (pinfunction "2_2") (pintype "passive"))
    )
    (net (code "55") (name "Net-(LED2-A)") (class "Default")
      (node (ref "LED2") (pin "1") (pinfunction "A_1") (pintype "passive"))
      (node (ref "R14") (pin "2") (pinfunction "2_2") (pintype "passive"))
    )
    (net (code "56") (name "Net-(U1-CPH)") (class "Default")
      (node (ref "C1") (pin "2") (pinfunction "2_2") (pintype "passive"))
      (node (ref "U1") (pin "6") (pinfunction "CPH_6") (pintype "passive"))
    )
    (net (code "57") (name "Net-(U1-CPL)") (class "Default")
      (node (ref "C1") (pin "1") (pinfunction "1_1") (pintype "passive"))
      (node (ref "U1") (pin "5") (pinfunction "CPL_5") (pintype "passive"))
    )
    (net (code "58") (name "Net-(U1-IN1)") (class "Default")
      (node (ref "R23") (pin "2") (pinfunction "2_2") (pintype "passive"))
      (node (ref "U1") (pin "2") (pinfunction "IN1_2") (pintype "passive"))
    )
    (net (code "59") (name "Net-(U1-IN2)") (class "Default")
      (node (ref "R24") (pin "2") (pinfunction "2_2") (pintype "passive"))
      (node (ref "U1") (pin "36") (pinfunction "IN2_36") (pintype "passive"))
    )
    (net (code "60") (name "Net-(U1-IN3)") (class "Default")
      (node (ref "R25") (pin "2") (pinfunction "2_2") (pintype "passive"))
      (node (ref "U1") (pin "34") (pinfunction "IN3_34") (pintype "passive"))
    )
    (net (code "61") (name "Net-(U1-VCP)") (class "Default")
      (node (ref "C6") (pin "2") (pinfunction "2_2") (pintype "passive"))
      (node (ref "U1") (pin "7") (pinfunction "VCP_7") (pintype "passive"))
    )
    (net (code "62") (name "Net-(U1-nFAULT)") (class "Default")
      (node (ref "R28") (pin "2") (pinfunction "2_2") (pintype "passive"))
      (node (ref "U1") (pin "28") (pinfunction "nFAULT_28") (pintype "passive"))
    )
    (net (code "63") (name "Net-(U1-nRESET)") (class "Default")
      (node (ref "R26") (pin "2") (pinfunction "2_2") (pintype "passive"))
      (node (ref "U1") (pin "26") (pinfunction "nRESET_26") (pintype "passive"))
    )
    (net (code "64") (name "Net-(U1-nSLEEP)") (class "Default")
      (node (ref "R27") (pin "2") (pinfunction "2_2") (pintype "passive"))
      (node (ref "U1") (pin "27") (pinfunction "nSLEEP_27") (pintype "passive"))
    )
    (net (code "65") (name "Net-(U2A-BOOT0)") (class "Default")
      (node (ref "R7") (pin "1") (pinfunction "1_1") (pintype "passive"))
      (node (ref "U2") (pin "44") (pinfunction "BOOT0_44") (pintype "input"))
    )
    (net (code "66") (name "Net-(U2A-NRST)") (class "Default")
      (node (ref "C25") (pin "2") (pinfunction "2_2") (pintype "passive"))
      (node (ref "R9") (pin "1") (pinfunction "1_1") (pintype "passive"))
      (node (ref "SW1") (pin "1") (pinfunction "1_1") (pintype "passive"))
      (node (ref "U2") (pin "7") (pinfunction "NRST_7") (pintype "bidirectional"))
    )
    (net (code "67") (name "Net-(U2A-PD0-OSC_IN)") (class "Default")
      (node (ref "C22") (pin "2") (pinfunction "2_2") (pintype "passive"))
      (node (ref "U2") (pin "5") (pinfunction "PD0-OSC_IN_5") (pintype "bidirectional"))
      (node (ref "X1") (pin "1") (pinfunction "1_1") (pintype "passive"))
    )
    (net (code "68") (name "Net-(U2A-PD1)") (class "Default")
      (node (ref "C23") (pin "2") (pinfunction "2_2") (pintype "passive"))
      (node (ref "U2") (pin "6") (pinfunction "PD1_6") (pintype "bidirectional"))
      (node (ref "X1") (pin "3") (pinfunction "3_3") (pintype "passive"))
    )
    (net (code "69") (name "VCC_3V3") (class "Default")
      (node (ref "C16") (pin "2") (pinfunction "2_2") (pintype "passive"))
      (node (ref "C17") (pin "2") (pinfunction "2_2") (pintype "passive"))
      (node (ref "C18") (pin "2") (pinfunction "2_2") (pintype "passive"))
      (node (ref "C28") (pin "1") (pinfunction "1_1") (pintype "passive"))
      (node (ref "C7") (pin "2") (pinfunction "2_2") (pintype "passive"))
      (node (ref "C8") (pin "2") (pinfunction "2_2") (pintype "passive"))
      (node (ref "IC1") (pin "5") (pinfunction "VOUT_5") (pintype "passive"))
      (node (ref "JP3") (pin "12") (pinfunction "12_12") (pintype "passive"))
      (node (ref "R12") (pin "1") (pinfunction "1_1") (pintype "passive"))
      (node (ref "R14") (pin "1") (pinfunction "1_1") (pintype "passive"))
      (node (ref "R9") (pin "2") (pinfunction "2_2") (pintype "passive"))
      (node (ref "U2") (pin "1") (pinfunction "VBAT_1") (pintype "power_in"))
      (node (ref "U2") (pin "24") (pinfunction "VDD_1_24") (pintype "power_in"))
      (node (ref "U2") (pin "36") (pinfunction "VDD_2_36") (pintype "power_in"))
      (node (ref "U2") (pin "48") (pinfunction "VDD_3_48") (pintype "power_in"))
      (node (ref "U3") (pin "2") (pinfunction "HVPP_2") (pintype "passive"))
      (node (ref "U3") (pin "4") (pinfunction "VDD_4") (pintype "passive"))
    )
    (net (code "70") (name "unconnected-(IC1-NC-Pad4)") (class "Default")
      (node (ref "IC1") (pin "4") (pinfunction "NC_4") (pintype "passive+no_connect"))
    )
    (net (code "71") (name "unconnected-(IC3-NC-Pad4)") (class "Default")
      (node (ref "IC3") (pin "4") (pinfunction "NC_4") (pintype "passive+no_connect"))
    )
    (net (code "72") (name "unconnected-(IC7-VREF-Pad5)") (class "Default")
      (node (ref "IC7") (pin "5") (pinfunction "VREF_5") (pintype "passive+no_connect"))
    )
    (net (code "73") (name "unconnected-(U1-COMPN-Pad22)") (class "Default")
      (node (ref "U1") (pin "22") (pinfunction "COMPN_22") (pintype "passive+no_connect"))
    )
    (net (code "74") (name "unconnected-(U1-COMPP-Pad21)") (class "Default")
      (node (ref "U1") (pin "21") (pinfunction "COMPP_21") (pintype "passive+no_connect"))
    )
    (net (code "75") (name "unconnected-(U1-NC-Pad4)") (class "Default")
      (node (ref "U1") (pin "4") (pinfunction "NC_4") (pintype "passive+no_connect"))
    )
    (net (code "76") (name "unconnected-(U1-NC-Pad8)") (class "Default")
      (node (ref "U1") (pin "8") (pinfunction "NC_8") (pintype "passive+no_connect"))
    )
    (net (code "77") (name "unconnected-(U1-NC-Pad14)") (class "Default")
      (node (ref "U1") (pin "14") (pinfunction "NC_14") (pintype "passive+no_connect"))
    )
    (net (code "78") (name "unconnected-(U1-V3P3-Pad25)") (class "Default")
      (node (ref "U1") (pin "25") (pinfunction "V3P3_25") (pintype "passive+no_connect"))
    )
    (net (code "79") (name "unconnected-(U1-nCOMPO-Pad29)") (class "Default")
      (node (ref "U1") (pin "29") (pinfunction "nCOMPO_29") (pintype "passive+no_connect"))
    )
    (net (code "80") (name "unconnected-(U2A-PA3-Pad13)") (class "Default")
      (node (ref "U2") (pin "13") (pinfunction "PA3_13") (pintype "bidirectional+no_connect"))
    )
    (net (code "81") (name "unconnected-(U2A-PB13-Pad26)") (class "Default")
      (node (ref "U2") (pin "26") (pinfunction "PB13_26") (pintype "bidirectional+no_connect"))
    )
    (net (code "82") (name "unconnected-(U2A-PB14-Pad27)") (class "Default")
      (node (ref "U2") (pin "27") (pinfunction "PB14_27") (pintype "bidirectional+no_connect"))
    )
    (net (code "83") (name "unconnected-(U2A-PB15-Pad28)") (class "Default")
      (node (ref "U2") (pin "28") (pinfunction "PB15_28") (pintype "bidirectional+no_connect"))
    )
    (net (code "84") (name "unconnected-(U2A-PC13-TAMPER-RTC-Pad2)") (class "Default")
      (node (ref "U2") (pin "2") (pinfunction "PC13-TAMPER-RTC_2") (pintype "bidirectional+no_connect"))
    )
    (net (code "85") (name "unconnected-(U2A-PC14-OSC32_IN-Pad3)") (class "Default")
      (node (ref "U2") (pin "3") (pinfunction "PC14-OSC32_IN_3") (pintype "bidirectional+no_connect"))
    )
    (net (code "86") (name "unconnected-(U2A-PC15-OSC32_OUT-Pad4)") (class "Default")
      (node (ref "U2") (pin "4") (pinfunction "PC15-OSC32_OUT_4") (pintype "bidirectional+no_connect"))
    )
    (net (code "87") (name "unconnected-(U3-OUT-Pad3)") (class "Default")
      (node (ref "U3") (pin "3") (pinfunction "OUT_3") (pintype "passive+no_connect"))
    )
  )
)
